# low-energy-meter.net
KiCad netlist of a schematic drawn in EAGLE
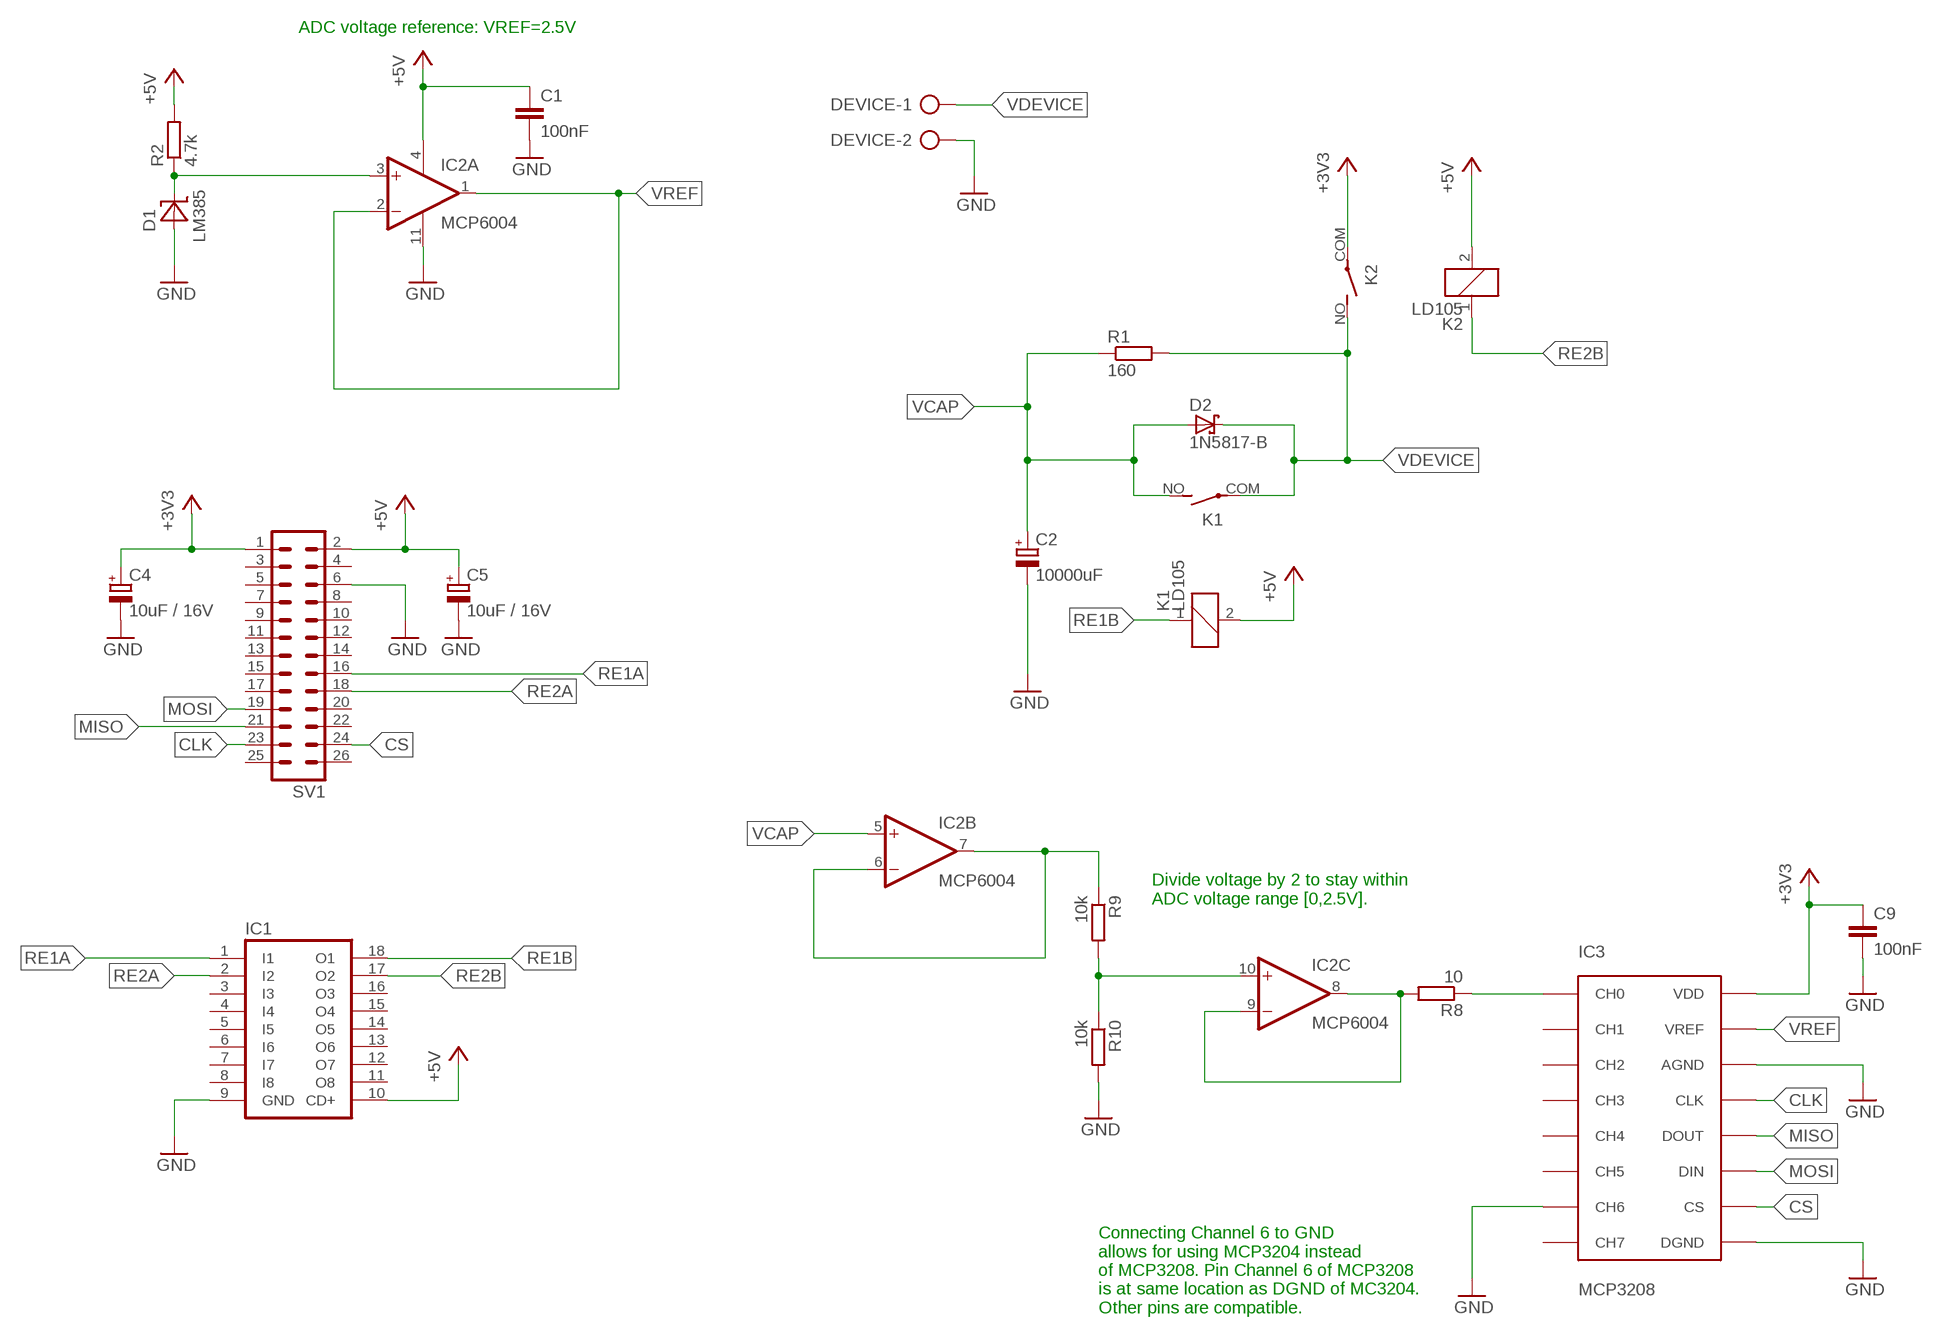
[diagram p0: schematic, sheet 1]

(export (version "E")
  (design (tool "Eeschema 10.0.6"))
  (components
    (comp (ref "C1")
      (value "100nF")
      (footprint "eagle-import:C050-024X044")
      (libsource (lib "eagle-import") (part "C-EU050-024X044"))
    )
    (comp (ref "C2")
      (value "10000uF")
      (footprint "eagle-import:E7,5-18")
      (libsource (lib "eagle-import") (part "CPOL-EUE7.5-18"))
    )
    (comp (ref "C4")
      (value "10uF / 16V")
      (footprint "eagle-import:E2,5-6")
      (libsource (lib "eagle-import") (part "CPOL-EUE2.5-6"))
    )
    (comp (ref "C5")
      (value "10uF / 16V")
      (footprint "eagle-import:E2,5-6")
      (libsource (lib "eagle-import") (part "CPOL-EUE2.5-6"))
    )
    (comp (ref "C9")
      (value "100nF")
      (footprint "eagle-import:C050-024X044")
      (libsource (lib "eagle-import") (part "C-EU050-024X044"))
    )
    (comp (ref "D1")
      (value "LM385")
      (footprint "eagle-import:TO-92")
      (libsource (lib "eagle-import") (part "LM385"))
    )
    (comp (ref "D2")
      (value "1N5817-B")
      (footprint "eagle-import:DO41-7.6")
      (libsource (lib "eagle-import") (part "1N5817-B"))
    )
    (comp (ref "DEVICE")
      (value "AK500/2")
      (footprint "eagle-import:AK500_2")
      (libsource (lib "eagle-import") (part "AK500/2"))
    )
    (comp (ref "IC1")
      (value "ULN2803A")
      (footprint "eagle-import:DIL18")
      (libsource (lib "eagle-import") (part "ULN2803A"))
    )
    (comp (ref "IC2")
      (value "MCP6004")
      (footprint "eagle-import:DIL14")
      (libsource (lib "eagle-import") (part "LM324N"))
    )
    (comp (ref "IC3")
      (value "MCP3208")
      (footprint "eagle-import:DIL16")
      (libsource (lib "eagle-import") (part "MCP3208"))
    )
    (comp (ref "K1")
      (value "LD105")
      (footprint "eagle-import:LD")
      (libsource (lib "eagle-import") (part "LD?105"))
    )
    (comp (ref "K2")
      (value "LD105")
      (footprint "eagle-import:LD")
      (libsource (lib "eagle-import") (part "LD?105"))
    )
    (comp (ref "R1")
      (value "160")
      (footprint "eagle-import:0207_7")
      (libsource (lib "eagle-import") (part "R-EU_0207/7"))
    )
    (comp (ref "R2")
      (value "4.7k")
      (footprint "eagle-import:0207_7")
      (libsource (lib "eagle-import") (part "R-EU_0207/7"))
    )
    (comp (ref "R8")
      (value "10")
      (footprint "eagle-import:0207_7")
      (libsource (lib "eagle-import") (part "R-EU_0207/7"))
    )
    (comp (ref "R9")
      (value "10k")
      (footprint "eagle-import:0207_7")
      (libsource (lib "eagle-import") (part "R-EU_0207/7"))
    )
    (comp (ref "R10")
      (value "10k")
      (footprint "eagle-import:0207_7")
      (libsource (lib "eagle-import") (part "R-EU_0207/7"))
    )
    (comp (ref "SV1")
      (value "ML26")
      (footprint "eagle-import:ML26")
      (libsource (lib "eagle-import") (part "ML26"))
    )
  )
  (nets
    (net (code "1") (name "+3V3") (class "Default")
      (node (ref "C4") (pin "+") (pinfunction "+_+") (pintype "passive"))
      (node (ref "C9") (pin "1") (pinfunction "1_1") (pintype "passive"))
      (node (ref "IC3") (pin "VDD") (pinfunction "VDD_VDD") (pintype "power_in"))
      (node (ref "K2") (pin "COM") (pinfunction "P_COM") (pintype "passive"))
      (node (ref "SV1") (pin "1") (pinfunction "1_1") (pintype "passive"))
    )
    (net (code "2") (name "+5V") (class "Default")
      (node (ref "C1") (pin "1") (pinfunction "1_1") (pintype "passive"))
      (node (ref "C5") (pin "+") (pinfunction "+_+") (pintype "passive"))
      (node (ref "IC1") (pin "10") (pinfunction "CD+_10") (pintype "passive"))
      (node (ref "IC2") (pin "4") (pinfunction "V+_4") (pintype "power_in"))
      (node (ref "K1") (pin "2") (pinfunction "2_2") (pintype "passive"))
      (node (ref "K2") (pin "2") (pinfunction "2_2") (pintype "passive"))
      (node (ref "R2") (pin "2") (pinfunction "2_2") (pintype "passive"))
      (node (ref "SV1") (pin "2") (pinfunction "2_2") (pintype "passive"))
    )
    (net (code "3") (name "CLK") (class "Default")
      (node (ref "IC3") (pin "CLK") (pinfunction "CLK_CLK") (pintype "input"))
      (node (ref "SV1") (pin "23") (pinfunction "23_23") (pintype "passive"))
    )
    (net (code "4") (name "CS") (class "Default")
      (node (ref "IC3") (pin "CS") (pinfunction "CS_CS") (pintype "input"))
      (node (ref "SV1") (pin "24") (pinfunction "24_24") (pintype "passive"))
    )
    (net (code "5") (name "GND") (class "Default")
      (node (ref "C1") (pin "2") (pinfunction "2_2") (pintype "passive"))
      (node (ref "C2") (pin "-") (pinfunction "-_-") (pintype "passive"))
      (node (ref "C4") (pin "-") (pinfunction "-_-") (pintype "passive"))
      (node (ref "C5") (pin "-") (pinfunction "-_-") (pintype "passive"))
      (node (ref "C9") (pin "2") (pinfunction "2_2") (pintype "passive"))
      (node (ref "D1") (pin "+") (pinfunction "+_+") (pintype "passive"))
      (node (ref "DEVICE") (pin "2") (pinfunction "KL_2") (pintype "passive"))
      (node (ref "IC1") (pin "9") (pinfunction "GND_9") (pintype "power_in"))
      (node (ref "IC2") (pin "11") (pinfunction "V-_11") (pintype "power_in"))
      (node (ref "IC3") (pin "AGND") (pinfunction "AGND_AGND") (pintype "power_in"))
      (node (ref "IC3") (pin "CH6") (pinfunction "CH6_CH6") (pintype "input"))
      (node (ref "IC3") (pin "DGND") (pinfunction "DGND_DGND") (pintype "power_in"))
      (node (ref "R10") (pin "2") (pinfunction "2_2") (pintype "passive"))
      (node (ref "SV1") (pin "6") (pinfunction "6_6") (pintype "passive"))
    )
    (net (code "6") (name "MISO") (class "Default")
      (node (ref "IC3") (pin "DOUT") (pinfunction "DOUT_DOUT") (pintype "output"))
      (node (ref "SV1") (pin "21") (pinfunction "21_21") (pintype "passive"))
    )
    (net (code "7") (name "MOSI") (class "Default")
      (node (ref "IC3") (pin "DIN") (pinfunction "DIN_DIN") (pintype "input"))
      (node (ref "SV1") (pin "19") (pinfunction "19_19") (pintype "passive"))
    )
    (net (code "8") (name "Net-(IC2A-+IN)") (class "Default")
      (node (ref "D1") (pin "-") (pinfunction "-_-") (pintype "passive"))
      (node (ref "IC2") (pin "3") (pinfunction "+IN_3") (pintype "input"))
      (node (ref "R2") (pin "1") (pinfunction "1_1") (pintype "passive"))
    )
    (net (code "9") (name "Net-(IC2B--IN)") (class "Default")
      (node (ref "IC2") (pin "6") (pinfunction "-IN_6") (pintype "input"))
      (node (ref "IC2") (pin "7") (pinfunction "OUT_7") (pintype "output"))
      (node (ref "R9") (pin "1") (pinfunction "1_1") (pintype "passive"))
    )
    (net (code "10") (name "Net-(IC2C-+IN)") (class "Default")
      (node (ref "IC2") (pin "10") (pinfunction "+IN_10") (pintype "input"))
      (node (ref "R10") (pin "1") (pinfunction "1_1") (pintype "passive"))
      (node (ref "R9") (pin "2") (pinfunction "2_2") (pintype "passive"))
    )
    (net (code "11") (name "Net-(IC2C--IN)") (class "Default")
      (node (ref "IC2") (pin "8") (pinfunction "OUT_8") (pintype "output"))
      (node (ref "IC2") (pin "9") (pinfunction "-IN_9") (pintype "input"))
      (node (ref "R8") (pin "2") (pinfunction "2_2") (pintype "passive"))
    )
    (net (code "12") (name "Net-(IC3-PadCH0)") (class "Default")
      (node (ref "IC3") (pin "CH0") (pinfunction "CH0_CH0") (pintype "input"))
      (node (ref "R8") (pin "1") (pinfunction "1_1") (pintype "passive"))
    )
    (net (code "13") (name "RE1A") (class "Default")
      (node (ref "IC1") (pin "1") (pinfunction "I1_1") (pintype "input"))
      (node (ref "SV1") (pin "16") (pinfunction "16_16") (pintype "passive"))
    )
    (net (code "14") (name "RE1B") (class "Default")
      (node (ref "IC1") (pin "18") (pinfunction "O1_18") (pintype "open_collector"))
      (node (ref "K1") (pin "1") (pinfunction "1_1") (pintype "passive"))
    )
    (net (code "15") (name "RE2A") (class "Default")
      (node (ref "IC1") (pin "2") (pinfunction "I2_2") (pintype "input"))
      (node (ref "SV1") (pin "18") (pinfunction "18_18") (pintype "passive"))
    )
    (net (code "16") (name "RE2B") (class "Default")
      (node (ref "IC1") (pin "17") (pinfunction "O2_17") (pintype "open_collector"))
      (node (ref "K2") (pin "1") (pinfunction "1_1") (pintype "passive"))
    )
    (net (code "17") (name "VCAP") (class "Default")
      (node (ref "C2") (pin "+") (pinfunction "+_+") (pintype "passive"))
      (node (ref "D2") (pin "A") (pinfunction "A_A") (pintype "passive"))
      (node (ref "IC2") (pin "5") (pinfunction "+IN_5") (pintype "input"))
      (node (ref "K1") (pin "NO") (pinfunction "S_NO") (pintype "passive"))
      (node (ref "R1") (pin "1") (pinfunction "1_1") (pintype "passive"))
    )
    (net (code "18") (name "VDEVICE") (class "Default")
      (node (ref "D2") (pin "C") (pinfunction "C_C") (pintype "passive"))
      (node (ref "DEVICE") (pin "1") (pinfunction "KL_1") (pintype "passive"))
      (node (ref "K1") (pin "COM") (pinfunction "P_COM") (pintype "passive"))
      (node (ref "K2") (pin "NO") (pinfunction "S_NO") (pintype "passive"))
      (node (ref "R1") (pin "2") (pinfunction "2_2") (pintype "passive"))
    )
    (net (code "19") (name "VREF") (class "Default")
      (node (ref "IC2") (pin "1") (pinfunction "OUT_1") (pintype "output"))
      (node (ref "IC2") (pin "2") (pinfunction "-IN_2") (pintype "input"))
      (node (ref "IC3") (pin "VREF") (pinfunction "VREF_VREF") (pintype "input"))
    )
    (net (code "20") (name "unconnected-(IC1-I3-Pad3)") (class "Default")
      (node (ref "IC1") (pin "3") (pinfunction "I3_3") (pintype "input"))
    )
    (net (code "21") (name "unconnected-(IC1-I4-Pad4)") (class "Default")
      (node (ref "IC1") (pin "4") (pinfunction "I4_4") (pintype "input"))
    )
    (net (code "22") (name "unconnected-(IC1-I5-Pad5)") (class "Default")
      (node (ref "IC1") (pin "5") (pinfunction "I5_5") (pintype "input"))
    )
    (net (code "23") (name "unconnected-(IC1-I6-Pad6)") (class "Default")
      (node (ref "IC1") (pin "6") (pinfunction "I6_6") (pintype "input"))
    )
    (net (code "24") (name "unconnected-(IC1-I7-Pad7)") (class "Default")
      (node (ref "IC1") (pin "7") (pinfunction "I7_7") (pintype "input"))
    )
    (net (code "25") (name "unconnected-(IC1-I8-Pad8)") (class "Default")
      (node (ref "IC1") (pin "8") (pinfunction "I8_8") (pintype "input"))
    )
    (net (code "26") (name "unconnected-(IC1-O3-Pad16)") (class "Default")
      (node (ref "IC1") (pin "16") (pinfunction "O3_16") (pintype "open_collector"))
    )
    (net (code "27") (name "unconnected-(IC1-O4-Pad15)") (class "Default")
      (node (ref "IC1") (pin "15") (pinfunction "O4_15") (pintype "open_collector"))
    )
    (net (code "28") (name "unconnected-(IC1-O5-Pad14)") (class "Default")
      (node (ref "IC1") (pin "14") (pinfunction "O5_14") (pintype "open_collector"))
    )
    (net (code "29") (name "unconnected-(IC1-O6-Pad13)") (class "Default")
      (node (ref "IC1") (pin "13") (pinfunction "O6_13") (pintype "open_collector"))
    )
    (net (code "30") (name "unconnected-(IC1-O7-Pad12)") (class "Default")
      (node (ref "IC1") (pin "12") (pinfunction "O7_12") (pintype "open_collector"))
    )
    (net (code "31") (name "unconnected-(IC1-O8-Pad11)") (class "Default")
      (node (ref "IC1") (pin "11") (pinfunction "O8_11") (pintype "open_collector"))
    )
    (net (code "32") (name "unconnected-(IC3-PadCH1)") (class "Default")
      (node (ref "IC3") (pin "CH1") (pinfunction "CH1_CH1") (pintype "input"))
    )
    (net (code "33") (name "unconnected-(IC3-PadCH2)") (class "Default")
      (node (ref "IC3") (pin "CH2") (pinfunction "CH2_CH2") (pintype "input"))
    )
    (net (code "34") (name "unconnected-(IC3-PadCH3)") (class "Default")
      (node (ref "IC3") (pin "CH3") (pinfunction "CH3_CH3") (pintype "input"))
    )
    (net (code "35") (name "unconnected-(IC3-PadCH4)") (class "Default")
      (node (ref "IC3") (pin "CH4") (pinfunction "CH4_CH4") (pintype "input"))
    )
    (net (code "36") (name "unconnected-(IC3-PadCH5)") (class "Default")
      (node (ref "IC3") (pin "CH5") (pinfunction "CH5_CH5") (pintype "input"))
    )
    (net (code "37") (name "unconnected-(IC3-PadCH7)") (class "Default")
      (node (ref "IC3") (pin "CH7") (pinfunction "CH7_CH7") (pintype "input"))
    )
    (net (code "38") (name "unconnected-(SV1-Pad3)") (class "Default")
      (node (ref "SV1") (pin "3") (pinfunction "3_3") (pintype "passive"))
    )
    (net (code "39") (name "unconnected-(SV1-Pad4)") (class "Default")
      (node (ref "SV1") (pin "4") (pinfunction "4_4") (pintype "passive"))
    )
    (net (code "40") (name "unconnected-(SV1-Pad5)") (class "Default")
      (node (ref "SV1") (pin "5") (pinfunction "5_5") (pintype "passive"))
    )
    (net (code "41") (name "unconnected-(SV1-Pad7)") (class "Default")
      (node (ref "SV1") (pin "7") (pinfunction "7_7") (pintype "passive"))
    )
    (net (code "42") (name "unconnected-(SV1-Pad8)") (class "Default")
      (node (ref "SV1") (pin "8") (pinfunction "8_8") (pintype "passive"))
    )
    (net (code "43") (name "unconnected-(SV1-Pad9)") (class "Default")
      (node (ref "SV1") (pin "9") (pinfunction "9_9") (pintype "passive"))
    )
    (net (code "44") (name "unconnected-(SV1-Pad10)") (class "Default")
      (node (ref "SV1") (pin "10") (pinfunction "10_10") (pintype "passive"))
    )
    (net (code "45") (name "unconnected-(SV1-Pad11)") (class "Default")
      (node (ref "SV1") (pin "11") (pinfunction "11_11") (pintype "passive"))
    )
    (net (code "46") (name "unconnected-(SV1-Pad12)") (class "Default")
      (node (ref "SV1") (pin "12") (pinfunction "12_12") (pintype "passive"))
    )
    (net (code "47") (name "unconnected-(SV1-Pad13)") (class "Default")
      (node (ref "SV1") (pin "13") (pinfunction "13_13") (pintype "passive"))
    )
    (net (code "48") (name "unconnected-(SV1-Pad14)") (class "Default")
      (node (ref "SV1") (pin "14") (pinfunction "14_14") (pintype "passive"))
    )
    (net (code "49") (name "unconnected-(SV1-Pad15)") (class "Default")
      (node (ref "SV1") (pin "15") (pinfunction "15_15") (pintype "passive"))
    )
    (net (code "50") (name "unconnected-(SV1-Pad17)") (class "Default")
      (node (ref "SV1") (pin "17") (pinfunction "17_17") (pintype "passive"))
    )
    (net (code "51") (name "unconnected-(SV1-Pad20)") (class "Default")
      (node (ref "SV1") (pin "20") (pinfunction "20_20") (pintype "passive"))
    )
    (net (code "52") (name "unconnected-(SV1-Pad22)") (class "Default")
      (node (ref "SV1") (pin "22") (pinfunction "22_22") (pintype "passive"))
    )
    (net (code "53") (name "unconnected-(SV1-Pad25)") (class "Default")
      (node (ref "SV1") (pin "25") (pinfunction "25_25") (pintype "passive"))
    )
    (net (code "54") (name "unconnected-(SV1-Pad26)") (class "Default")
      (node (ref "SV1") (pin "26") (pinfunction "26_26") (pintype "passive"))
    )
  )
)
